# gk_midi_module.net
KiCad netlist of a schematic drawn in EAGLE
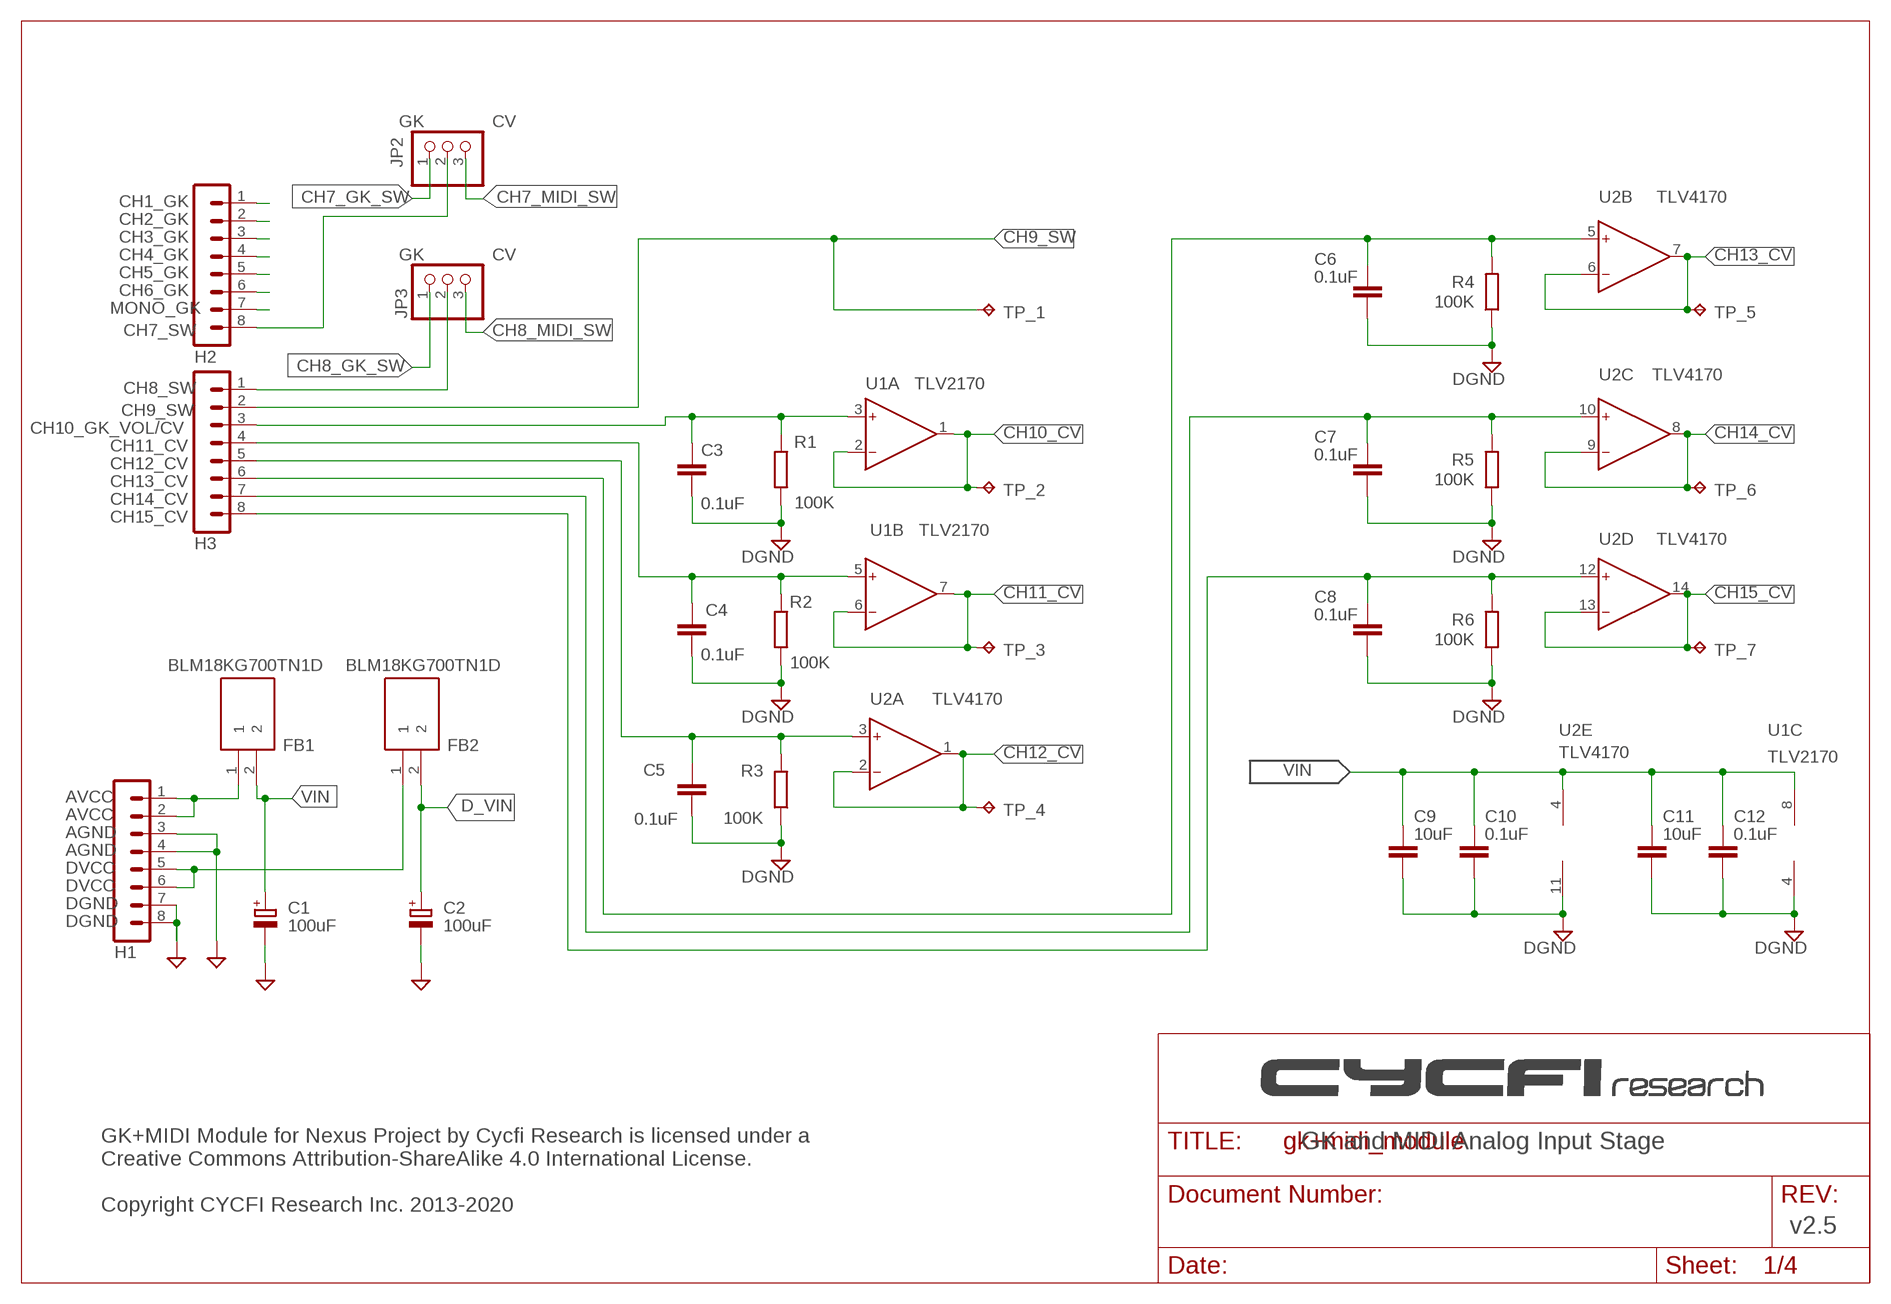
[diagram p0: schematic, sheet 1]
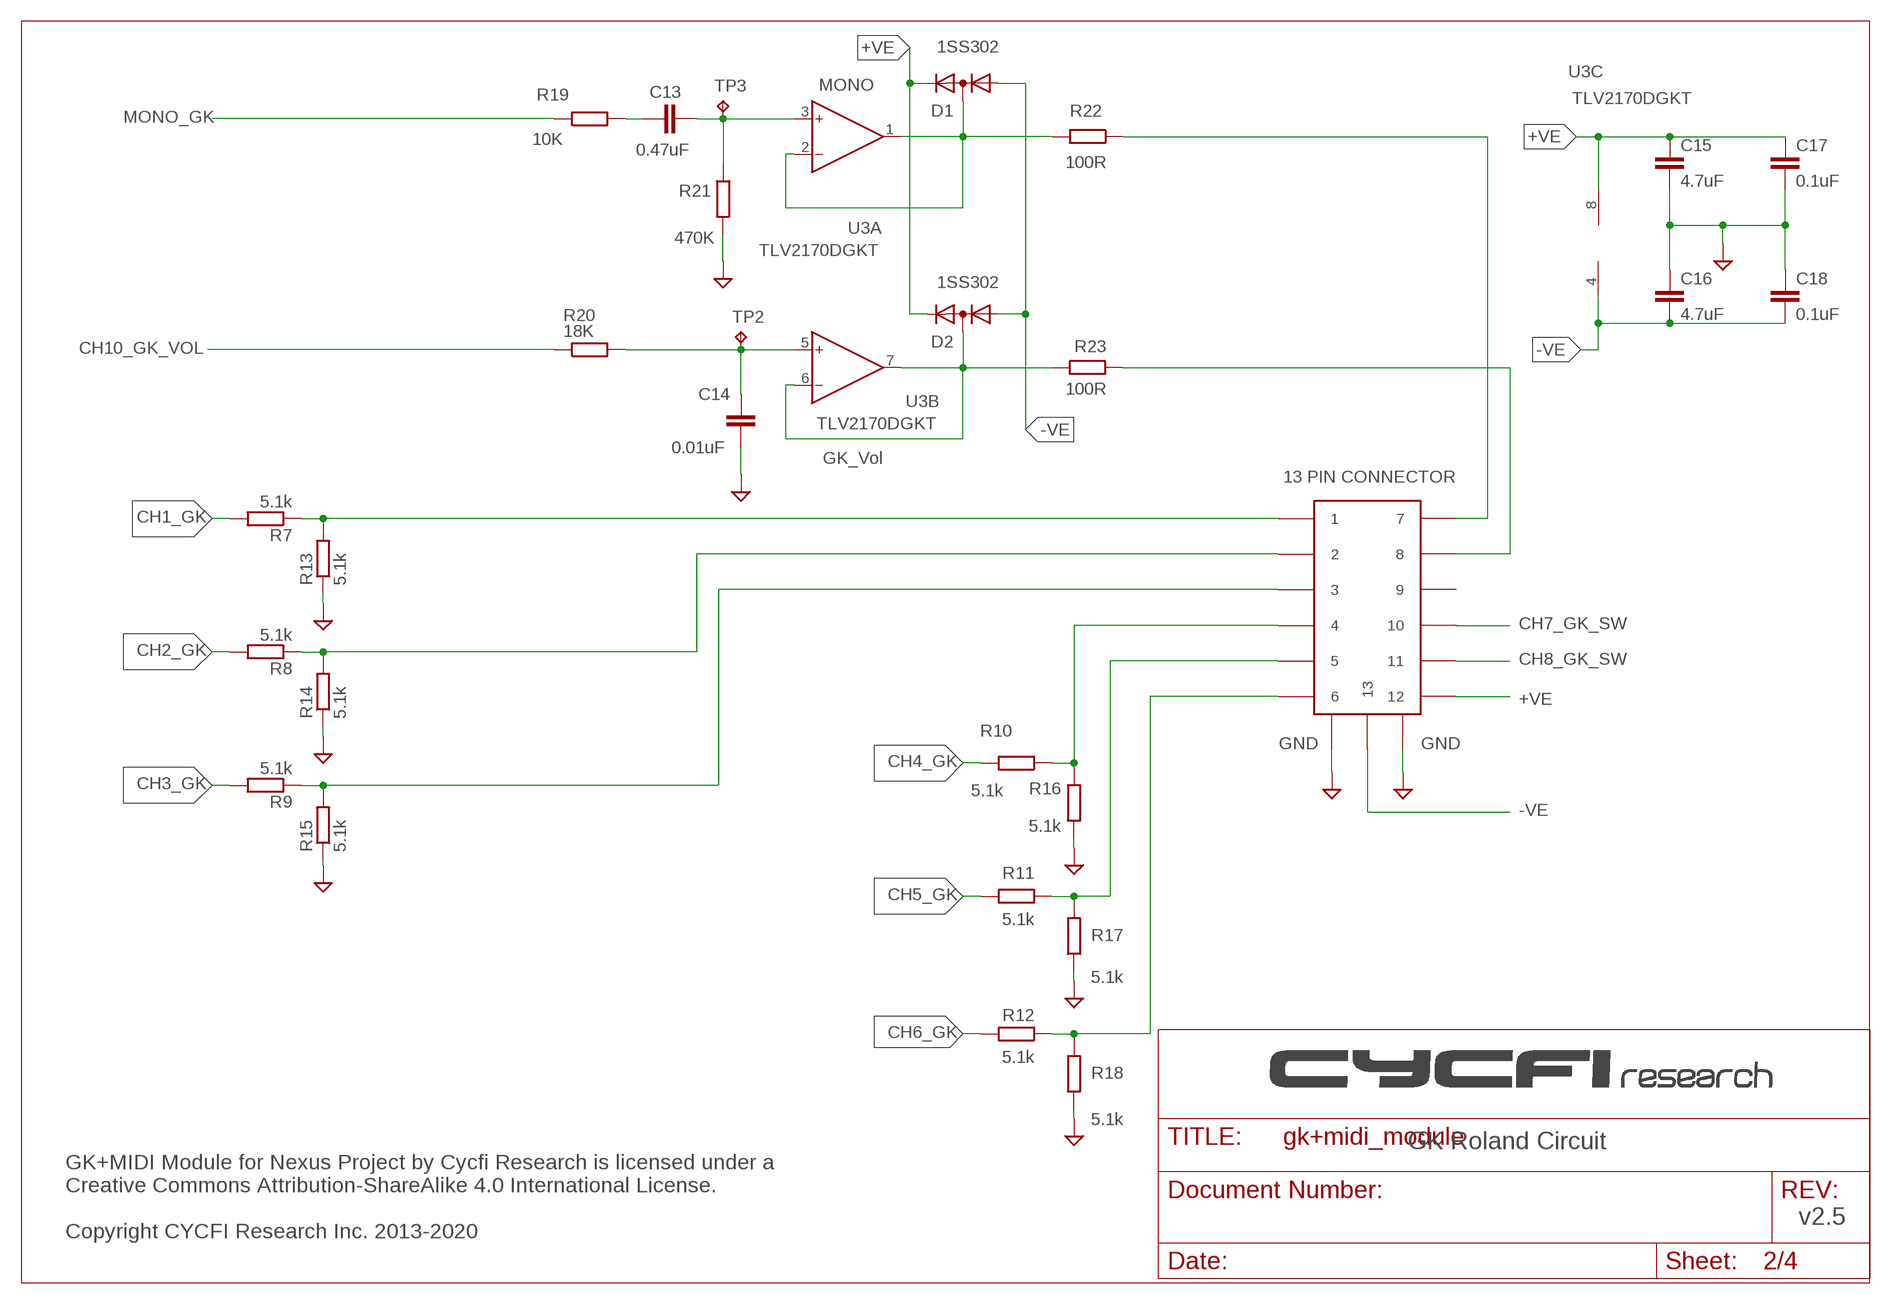
[diagram p1: schematic, sheet 2]
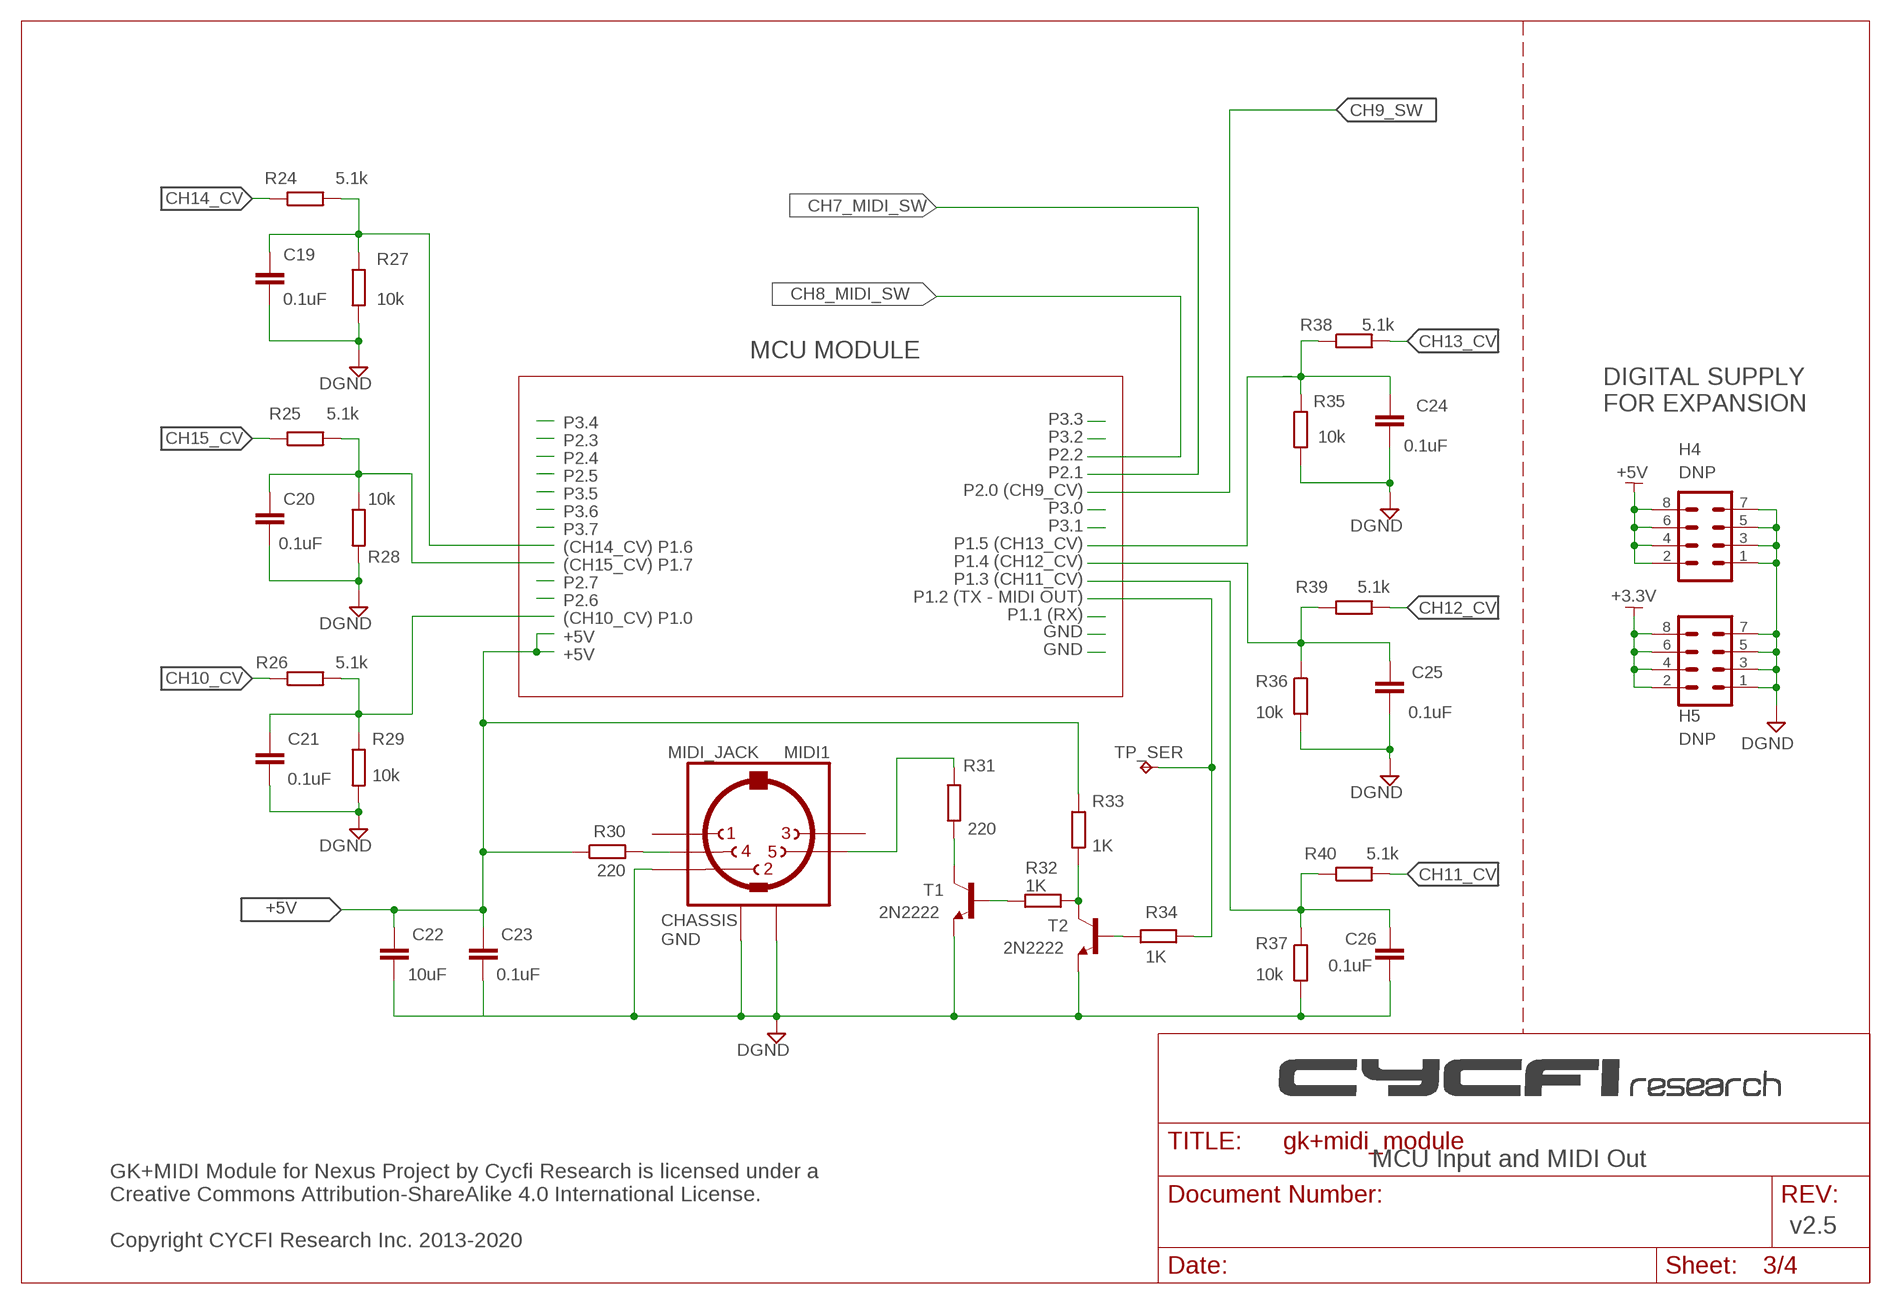
[diagram p2: schematic, sheet 3]
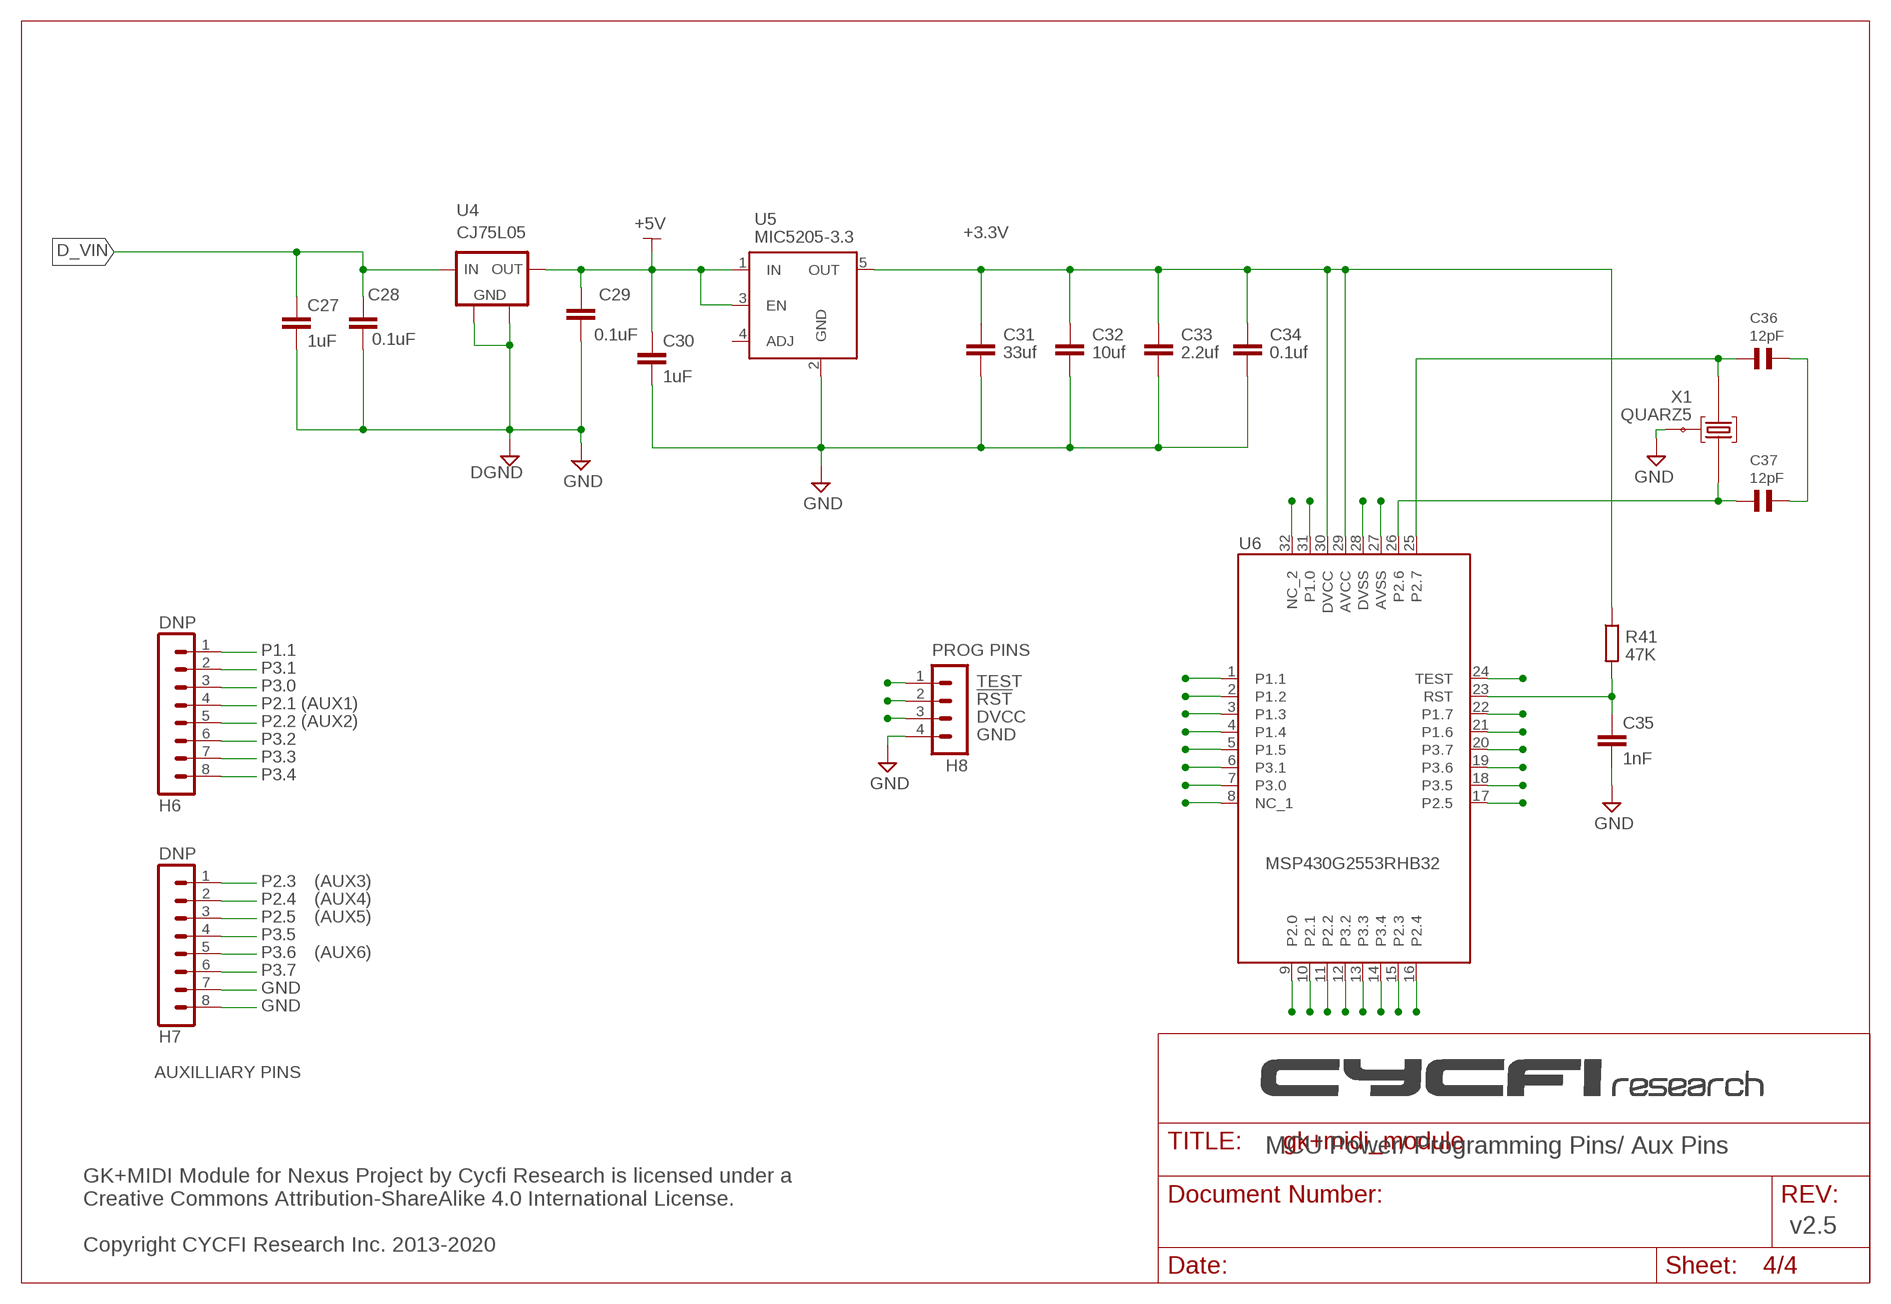
[diagram p3: schematic, sheet 4]

(export (version "E")
  (design (tool "Eeschema 10.0.6"))
  (components
    (comp (ref "C27")
      (value "1uF")
      (footprint "eagle-import:C0402")
      (libsource (lib "eagle-import") (part "C-EUC0402"))
    )
    (comp (ref "C28")
      (value "0.1uF")
      (footprint "eagle-import:C0603")
      (libsource (lib "eagle-import") (part "C-EUC0603"))
    )
    (comp (ref "C29")
      (value "0.1uF")
      (footprint "eagle-import:C0603")
      (libsource (lib "eagle-import") (part "C-EUC0603"))
    )
    (comp (ref "C30")
      (value "1uF")
      (footprint "eagle-import:C0402")
      (libsource (lib "eagle-import") (part "C-EUC0402"))
    )
    (comp (ref "C31")
      (value "33uf")
      (footprint "eagle-import:C0805")
      (libsource (lib "eagle-import") (part "C-EUC0805"))
    )
    (comp (ref "C32")
      (value "10uf")
      (footprint "eagle-import:C0805")
      (libsource (lib "eagle-import") (part "C-EUC0805"))
    )
    (comp (ref "C33")
      (value "2.2uf")
      (footprint "eagle-import:C0805")
      (libsource (lib "eagle-import") (part "C-EUC0805"))
    )
    (comp (ref "C34")
      (value "0.1uf")
      (footprint "eagle-import:C0603")
      (libsource (lib "eagle-import") (part "C-EUC0603"))
    )
    (comp (ref "C35")
      (value "1nF")
      (footprint "eagle-import:C0402")
      (libsource (lib "eagle-import") (part "C-EUC0402"))
    )
    (comp (ref "C36")
      (value "12pF")
      (footprint "eagle-import:0603")
      (libsource (lib "eagle-import") (part "C_SMD0603"))
    )
    (comp (ref "C37")
      (value "12pF")
      (footprint "eagle-import:0603")
      (libsource (lib "eagle-import") (part "C_SMD0603"))
    )
    (comp (ref "H6")
      (value "DNP")
      (footprint "eagle-import:MA08-1")
      (libsource (lib "eagle-import") (part "MA08-1"))
    )
    (comp (ref "H7")
      (value "DNP")
      (footprint "eagle-import:MA08-1")
      (libsource (lib "eagle-import") (part "MA08-1"))
    )
    (comp (ref "H8")
      (value "MA04-1")
      (footprint "eagle-import:MA04-1")
      (libsource (lib "eagle-import") (part "MA04-1"))
    )
    (comp (ref "R41")
      (value "47K")
      (footprint "eagle-import:R0402")
      (libsource (lib "eagle-import") (part "R-EU_R0402"))
    )
    (comp (ref "U4")
      (value "L78LXX")
      (footprint "eagle-import:SOT89")
      (libsource (lib "eagle-import") (part "L78LXX"))
    )
    (comp (ref "U5")
      (value "MIC5205-3.3")
      (footprint "eagle-import:SOT23-5")
      (fields (field (name "MF") "ALTERA CORPORATION") (field (name "MPN") "MIC5219BM5 TR"))
      (libsource (lib "eagle-import") (part "MIC5219BM5"))
    )
    (comp (ref "U6")
      (value "MSP430G2553RHB32")
      (footprint "eagle-import:QFN32")
      (libsource (lib "eagle-import") (part "MSP430G2553RHB32"))
    )
    (comp (ref "X1")
      (value "QUARZ5")
      (footprint "eagle-import:QUARZ5")
      (libsource (lib "eagle-import") (part "QUARZ5"))
    )
    (comp (ref "C1")
      (value "100uF")
      (footprint "eagle-import:153CLV-0505")
      (libsource (lib "eagle-import") (part "CPOL-EU153CLV-0505"))
    )
    (comp (ref "C2")
      (value "100uF")
      (footprint "eagle-import:153CLV-0505")
      (libsource (lib "eagle-import") (part "CPOL-EU153CLV-0505"))
    )
    (comp (ref "C3")
      (value "0.1uF")
      (footprint "eagle-import:C0603")
      (libsource (lib "eagle-import") (part "C-EUC0603"))
    )
    (comp (ref "C4")
      (value "0.1uF")
      (footprint "eagle-import:C0603")
      (libsource (lib "eagle-import") (part "C-EUC0603"))
    )
    (comp (ref "C5")
      (value "0.1uF")
      (footprint "eagle-import:C0603")
      (libsource (lib "eagle-import") (part "C-EUC0603"))
    )
    (comp (ref "C6")
      (value "0.1uF")
      (footprint "eagle-import:C0603")
      (libsource (lib "eagle-import") (part "C-EUC0603"))
    )
    (comp (ref "C7")
      (value "0.1uF")
      (footprint "eagle-import:C0603")
      (libsource (lib "eagle-import") (part "C-EUC0603"))
    )
    (comp (ref "C8")
      (value "0.1uF")
      (footprint "eagle-import:C0603")
      (libsource (lib "eagle-import") (part "C-EUC0603"))
    )
    (comp (ref "C9")
      (value "10uF")
      (footprint "eagle-import:C0805")
      (libsource (lib "eagle-import") (part "C-EUC0805"))
    )
    (comp (ref "C10")
      (value "0.1uF")
      (footprint "eagle-import:C0603")
      (libsource (lib "eagle-import") (part "C-EUC0603"))
    )
    (comp (ref "C11")
      (value "10uF")
      (footprint "eagle-import:C0805")
      (libsource (lib "eagle-import") (part "C-EUC0805"))
    )
    (comp (ref "C12")
      (value "0.1uF")
      (footprint "eagle-import:C0603")
      (libsource (lib "eagle-import") (part "C-EUC0603"))
    )
    (comp (ref "FB1")
      (value "BLM18KG700TN1D")
      (footprint "eagle-import:BEADC1608X75N")
      (fields (field (name "MOUSER_PART_NUMBER") "81-BLM18KG700TN1D"))
      (libsource (lib "eagle-import") (part "BLM18KG700TN1D"))
    )
    (comp (ref "FB2")
      (value "BLM18KG700TN1D")
      (footprint "eagle-import:BEADC1608X75N")
      (description "BLM18_N1D Series EMI Suppression Filter 70+/-25% at 100MHz 3.5A @85")
      (fields
        (field (name "MOUSER_PART_NUMBER") "81-BLM18KG700TN1D")
        (field (name "HEIGHT") "0.75mm")
        (field (name "MANUFACTURER_NAME") "Murata Electronics")
        (field (name "MANUFACTURER_PART_NUMBER") "BLM18KG700TN1D")
        (field (name "MOUSER_PART_NUMBER_1") "81-BLM18KG700TN1D")
        (field (name "MOUSER_PRICE-STOCK") "https://www.mouser.com/Search/Refine.aspx?Keyword=81-BLM18KG700TN1D")
      )
      (libsource (lib "eagle-import") (part "BLM18KG700TN1D"))
    )
    (comp (ref "H1")
      (value "MA08-1")
      (footprint "eagle-import:MA08-1")
      (libsource (lib "eagle-import") (part "MA08-1"))
    )
    (comp (ref "H2")
      (value "MA08-1")
      (footprint "eagle-import:MA08-1")
      (libsource (lib "eagle-import") (part "MA08-1"))
    )
    (comp (ref "H3")
      (value "MA08-1")
      (footprint "eagle-import:MA08-1")
      (libsource (lib "eagle-import") (part "MA08-1"))
    )
    (comp (ref "JP2")
      (value "PINHD-1X03_2.00")
      (footprint "eagle-import:1X03M")
      (libsource (lib "eagle-import") (part "PINHD-1X03_2.00"))
    )
    (comp (ref "JP3")
      (value "PINHD-1X03_2.00")
      (footprint "eagle-import:1X03M")
      (libsource (lib "eagle-import") (part "PINHD-1X03_2.00"))
    )
    (comp (ref "R1")
      (value "100K")
      (footprint "eagle-import:R0402")
      (libsource (lib "eagle-import") (part "R-EU_R0402"))
    )
    (comp (ref "R2")
      (value "100K")
      (footprint "eagle-import:R0402")
      (libsource (lib "eagle-import") (part "R-EU_R0402"))
    )
    (comp (ref "R3")
      (value "100K")
      (footprint "eagle-import:R0402")
      (libsource (lib "eagle-import") (part "R-EU_R0402"))
    )
    (comp (ref "R4")
      (value "100K")
      (footprint "eagle-import:R0402")
      (libsource (lib "eagle-import") (part "R-EU_R0402"))
    )
    (comp (ref "R5")
      (value "100K")
      (footprint "eagle-import:R0402")
      (libsource (lib "eagle-import") (part "R-EU_R0402"))
    )
    (comp (ref "R6")
      (value "100K")
      (footprint "eagle-import:R0402")
      (libsource (lib "eagle-import") (part "R-EU_R0402"))
    )
    (comp (ref "TP_1")
      (value "TPB1,27")
      (footprint "eagle-import:B1,27")
      (libsource (lib "eagle-import") (part "TPB1,27"))
    )
    (comp (ref "TP_2")
      (value "TPB1,27")
      (footprint "eagle-import:B1,27")
      (libsource (lib "eagle-import") (part "TPB1,27"))
    )
    (comp (ref "TP_3")
      (value "TPB1,27")
      (footprint "eagle-import:B1,27")
      (libsource (lib "eagle-import") (part "TPB1,27"))
    )
    (comp (ref "TP_4")
      (value "TPB1,27")
      (footprint "eagle-import:B1,27")
      (libsource (lib "eagle-import") (part "TPB1,27"))
    )
    (comp (ref "TP_5")
      (value "TPB1,27")
      (footprint "eagle-import:B1,27")
      (libsource (lib "eagle-import") (part "TPB1,27"))
    )
    (comp (ref "TP_6")
      (value "TPB1,27")
      (footprint "eagle-import:B1,27")
      (libsource (lib "eagle-import") (part "TPB1,27"))
    )
    (comp (ref "TP_7")
      (value "TPB1,27")
      (footprint "eagle-import:B1,27")
      (libsource (lib "eagle-import") (part "TPB1,27"))
    )
    (comp (ref "U1")
      (value "TLV2170DGKT")
      (footprint "eagle-import:MSOP8")
      (libsource (lib "eagle-import") (part "TLV2170DGKT"))
    )
    (comp (ref "U2")
      (value "LMV324")
      (footprint "eagle-import:SSOP-14")
      (libsource (lib "eagle-import") (part "LMV324"))
    )
    (comp (ref "C19")
      (value "0.1uF")
      (footprint "eagle-import:C0603")
      (libsource (lib "eagle-import") (part "C-EUC0603"))
    )
    (comp (ref "C20")
      (value "0.1uF")
      (footprint "eagle-import:C0603")
      (libsource (lib "eagle-import") (part "C-EUC0603"))
    )
    (comp (ref "C21")
      (value "0.1uF")
      (footprint "eagle-import:C0603")
      (libsource (lib "eagle-import") (part "C-EUC0603"))
    )
    (comp (ref "C22")
      (value "10uF")
      (footprint "eagle-import:C0805")
      (libsource (lib "eagle-import") (part "C-EUC0805"))
    )
    (comp (ref "C23")
      (value "0.1uF")
      (footprint "eagle-import:C0603")
      (libsource (lib "eagle-import") (part "C-EUC0603"))
    )
    (comp (ref "C24")
      (value "0.1uF")
      (footprint "eagle-import:C0603")
      (libsource (lib "eagle-import") (part "C-EUC0603"))
    )
    (comp (ref "C25")
      (value "0.1uF")
      (footprint "eagle-import:C0603")
      (libsource (lib "eagle-import") (part "C-EUC0603"))
    )
    (comp (ref "C26")
      (value "0.1uF")
      (footprint "eagle-import:C0603")
      (libsource (lib "eagle-import") (part "C-EUC0603"))
    )
    (comp (ref "H4")
      (value "DNP")
      (footprint "eagle-import:MA04-2")
      (libsource (lib "eagle-import") (part "MA04-2"))
    )
    (comp (ref "H5")
      (value "DNP")
      (footprint "eagle-import:MA04-2")
      (libsource (lib "eagle-import") (part "MA04-2"))
    )
    (comp (ref "MIDI1")
      (value "MIDI_JACK")
      (footprint "eagle-import:MIDI_JACK")
      (libsource (lib "eagle-import") (part "MIDI_JACK"))
    )
    (comp (ref "R24")
      (value "5.1k")
      (footprint "eagle-import:R0402")
      (libsource (lib "eagle-import") (part "R-EU_R0402"))
    )
    (comp (ref "R25")
      (value "5.1k")
      (footprint "eagle-import:R0402")
      (libsource (lib "eagle-import") (part "R-EU_R0402"))
    )
    (comp (ref "R26")
      (value "5.1k")
      (footprint "eagle-import:R0402")
      (libsource (lib "eagle-import") (part "R-EU_R0402"))
    )
    (comp (ref "R27")
      (value "10k")
      (footprint "eagle-import:R0402")
      (libsource (lib "eagle-import") (part "R-EU_R0402"))
    )
    (comp (ref "R28")
      (value "10k")
      (footprint "eagle-import:R0402")
      (libsource (lib "eagle-import") (part "R-EU_R0402"))
    )
    (comp (ref "R29")
      (value "10k")
      (footprint "eagle-import:R0402")
      (libsource (lib "eagle-import") (part "R-EU_R0402"))
    )
    (comp (ref "R30")
      (value "220")
      (footprint "eagle-import:R0402")
      (libsource (lib "eagle-import") (part "R-EU_R0402"))
    )
    (comp (ref "R31")
      (value "220")
      (footprint "eagle-import:R0402")
      (libsource (lib "eagle-import") (part "R-EU_R0402"))
    )
    (comp (ref "R32")
      (value "1K")
      (footprint "eagle-import:R0402")
      (libsource (lib "eagle-import") (part "R-EU_R0402"))
    )
    (comp (ref "R33")
      (value "1K")
      (footprint "eagle-import:R0402")
      (libsource (lib "eagle-import") (part "R-EU_R0402"))
    )
    (comp (ref "R34")
      (value "1K")
      (footprint "eagle-import:R0402")
      (libsource (lib "eagle-import") (part "R-EU_R0402"))
    )
    (comp (ref "R35")
      (value "10k")
      (footprint "eagle-import:R0402")
      (libsource (lib "eagle-import") (part "R-EU_R0402"))
    )
    (comp (ref "R36")
      (value "10k")
      (footprint "eagle-import:R0402")
      (libsource (lib "eagle-import") (part "R-EU_R0402"))
    )
    (comp (ref "R37")
      (value "10k")
      (footprint "eagle-import:R0402")
      (libsource (lib "eagle-import") (part "R-EU_R0402"))
    )
    (comp (ref "R38")
      (value "5.1k")
      (footprint "eagle-import:R0402")
      (libsource (lib "eagle-import") (part "R-EU_R0402"))
    )
    (comp (ref "R39")
      (value "5.1k")
      (footprint "eagle-import:R0402")
      (libsource (lib "eagle-import") (part "R-EU_R0402"))
    )
    (comp (ref "R40")
      (value "5.1k")
      (footprint "eagle-import:R0402")
      (libsource (lib "eagle-import") (part "R-EU_R0402"))
    )
    (comp (ref "T1")
      (value "2N2222")
      (footprint "eagle-import:SOT23-3")
      (libsource (lib "eagle-import") (part "TRAN-MMBT2222A"))
    )
    (comp (ref "T2")
      (value "2N2222")
      (footprint "eagle-import:SOT23-3")
      (libsource (lib "eagle-import") (part "TRAN-MMBT2222A"))
    )
    (comp (ref "TP_SER")
      (value "TPB1,27")
      (footprint "eagle-import:B1,27")
      (libsource (lib "eagle-import") (part "TPB1,27"))
    )
    (comp (ref "C13")
      (value "0.47uF")
      (footprint "eagle-import:C0603")
      (libsource (lib "eagle-import") (part "C-EUC0603"))
    )
    (comp (ref "C14")
      (value "0.01uF")
      (footprint "eagle-import:C0402")
      (libsource (lib "eagle-import") (part "C-EUC0402"))
    )
    (comp (ref "C15")
      (value "4.7uF")
      (footprint "eagle-import:C0603")
      (libsource (lib "eagle-import") (part "C-EUC0603"))
    )
    (comp (ref "C16")
      (value "4.7uF")
      (footprint "eagle-import:C0603")
      (libsource (lib "eagle-import") (part "C-EUC0603"))
    )
    (comp (ref "C17")
      (value "0.1uF")
      (footprint "eagle-import:C0603")
      (libsource (lib "eagle-import") (part "C-EUC0603"))
    )
    (comp (ref "C18")
      (value "0.1uF")
      (footprint "eagle-import:C0603")
      (libsource (lib "eagle-import") (part "C-EUC0603"))
    )
    (comp (ref "D1")
      (value "1SS302")
      (footprint "eagle-import:SC70-3")
      (libsource (lib "eagle-import") (part "1SS302"))
    )
    (comp (ref "D2")
      (value "1SS302")
      (footprint "eagle-import:SC70-3")
      (libsource (lib "eagle-import") (part "1SS302"))
    )
    (comp (ref "R7")
      (value "5.1k")
      (footprint "eagle-import:R0402")
      (libsource (lib "eagle-import") (part "R-EU_R0402"))
    )
    (comp (ref "R8")
      (value "5.1k")
      (footprint "eagle-import:R0402")
      (libsource (lib "eagle-import") (part "R-EU_R0402"))
    )
    (comp (ref "R9")
      (value "5.1k")
      (footprint "eagle-import:R0402")
      (libsource (lib "eagle-import") (part "R-EU_R0402"))
    )
    (comp (ref "R10")
      (value "5.1k")
      (footprint "eagle-import:R0402")
      (libsource (lib "eagle-import") (part "R-EU_R0402"))
    )
    (comp (ref "R11")
      (value "5.1k")
      (footprint "eagle-import:R0402")
      (libsource (lib "eagle-import") (part "R-EU_R0402"))
    )
    (comp (ref "R12")
      (value "5.1k")
      (footprint "eagle-import:R0402")
      (libsource (lib "eagle-import") (part "R-EU_R0402"))
    )
    (comp (ref "R13")
      (value "5.1k")
      (footprint "eagle-import:R0402")
      (libsource (lib "eagle-import") (part "R-EU_R0402"))
    )
    (comp (ref "R14")
      (value "5.1k")
      (footprint "eagle-import:R0402")
      (libsource (lib "eagle-import") (part "R-EU_R0402"))
    )
    (comp (ref "R15")
      (value "5.1k")
      (footprint "eagle-import:R0402")
      (libsource (lib "eagle-import") (part "R-EU_R0402"))
    )
    (comp (ref "R16")
      (value "5.1k")
      (footprint "eagle-import:R0402")
      (libsource (lib "eagle-import") (part "R-EU_R0402"))
    )
    (comp (ref "R17")
      (value "5.1k")
      (footprint "eagle-import:R0402")
      (libsource (lib "eagle-import") (part "R-EU_R0402"))
    )
    (comp (ref "R18")
      (value "5.1k")
      (footprint "eagle-import:R0402")
      (libsource (lib "eagle-import") (part "R-EU_R0402"))
    )
    (comp (ref "R19")
      (value "10K")
      (footprint "eagle-import:R0402")
      (libsource (lib "eagle-import") (part "R-EU_R0402"))
    )
    (comp (ref "R20")
      (value "18K")
      (footprint "eagle-import:R0402")
      (libsource (lib "eagle-import") (part "R-EU_R0402"))
    )
    (comp (ref "R21")
      (value "470K")
      (footprint "eagle-import:R0402")
      (libsource (lib "eagle-import") (part "R-EU_R0402"))
    )
    (comp (ref "R22")
      (value "100R")
      (footprint "eagle-import:R0402")
      (libsource (lib "eagle-import") (part "R-EU_R0402"))
    )
    (comp (ref "R23")
      (value "100R")
      (footprint "eagle-import:R0402")
      (libsource (lib "eagle-import") (part "R-EU_R0402"))
    )
    (comp (ref "TP2")
      (value "TPB1,27")
      (footprint "eagle-import:B1,27")
      (libsource (lib "eagle-import") (part "TPB1,27"))
    )
    (comp (ref "TP3")
      (value "TPB1,27")
      (footprint "eagle-import:B1,27")
      (libsource (lib "eagle-import") (part "TPB1,27"))
    )
    (comp (ref "U$1")
      (value "13P_MIDI_2")
      (footprint "eagle-import:13P-MIDI-2")
      (libsource (lib "eagle-import") (part "13P_MIDI_2"))
    )
    (comp (ref "U3")
      (value "TLV2170DGKT")
      (footprint "eagle-import:MSOP8")
      (libsource (lib "eagle-import") (part "TLV2170DGKT"))
    )
  )
  (nets
    (net (code "1") (name "+3.3V") (class "Default")
      (node (ref "C31") (pin "1") (pinfunction "1_1") (pintype "passive"))
      (node (ref "C32") (pin "1") (pinfunction "1_1") (pintype "passive"))
      (node (ref "C33") (pin "1") (pinfunction "1_1") (pintype "passive"))
      (node (ref "C34") (pin "1") (pinfunction "1_1") (pintype "passive"))
      (node (ref "H5") (pin "2") (pinfunction "2_2") (pintype "passive"))
      (node (ref "H5") (pin "4") (pinfunction "4_4") (pintype "passive"))
      (node (ref "H5") (pin "6") (pinfunction "6_6") (pintype "passive"))
      (node (ref "H5") (pin "8") (pinfunction "8_8") (pintype "passive"))
      (node (ref "H8") (pin "3") (pinfunction "3_3") (pintype "passive"))
      (node (ref "R41") (pin "1") (pinfunction "1_1") (pintype "passive"))
      (node (ref "U5") (pin "5") (pinfunction "OUT_5") (pintype "output"))
      (node (ref "U6") (pin "29") (pinfunction "AVCC_29") (pintype "bidirectional"))
      (node (ref "U6") (pin "30") (pinfunction "DVCC_30") (pintype "bidirectional"))
    )
    (net (code "2") (name "+5V") (class "Default")
      (node (ref "C22") (pin "1") (pinfunction "1_1") (pintype "passive"))
      (node (ref "C23") (pin "1") (pinfunction "1_1") (pintype "passive"))
      (node (ref "C29") (pin "1") (pinfunction "1_1") (pintype "passive"))
      (node (ref "C30") (pin "1") (pinfunction "1_1") (pintype "passive"))
      (node (ref "H4") (pin "2") (pinfunction "2_2") (pintype "passive"))
      (node (ref "H4") (pin "4") (pinfunction "4_4") (pintype "passive"))
      (node (ref "H4") (pin "6") (pinfunction "6_6") (pintype "passive"))
      (node (ref "H4") (pin "8") (pinfunction "8_8") (pintype "passive"))
      (node (ref "R30") (pin "1") (pinfunction "1_1") (pintype "passive"))
      (node (ref "R33") (pin "2") (pinfunction "2_2") (pintype "passive"))
      (node (ref "U4") (pin "1") (pinfunction "IN_1") (pintype "input"))
      (node (ref "U5") (pin "1") (pinfunction "IN_1") (pintype "input"))
      (node (ref "U5") (pin "3") (pinfunction "EN_3") (pintype "input"))
    )
    (net (code "3") (name "+VE") (class "Default")
      (node (ref "C15") (pin "1") (pinfunction "1_1") (pintype "passive"))
      (node (ref "C17") (pin "1") (pinfunction "1_1") (pintype "passive"))
      (node (ref "D1") (pin "2") (pinfunction "K_2") (pintype "passive"))
      (node (ref "D2") (pin "2") (pinfunction "K_2") (pintype "passive"))
      (node (ref "U$1") (pin "12") (pinfunction "12_12") (pintype "bidirectional"))
      (node (ref "U3") (pin "8") (pinfunction "V+_8") (pintype "power_in"))
    )
    (net (code "4") (name "-VE") (class "Default")
      (node (ref "C16") (pin "2") (pinfunction "2_2") (pintype "passive"))
      (node (ref "C18") (pin "2") (pinfunction "2_2") (pintype "passive"))
      (node (ref "D1") (pin "1") (pinfunction "A_1") (pintype "passive"))
      (node (ref "D2") (pin "1") (pinfunction "A_1") (pintype "passive"))
      (node (ref "U$1") (pin "13") (pinfunction "13_13") (pintype "bidirectional"))
      (node (ref "U3") (pin "4") (pinfunction "V-_4") (pintype "power_in"))
    )
    (net (code "5") (name "AVCC") (class "Default")
      (node (ref "FB1") (pin "1") (pinfunction "1_1") (pintype "bidirectional"))
      (node (ref "H1") (pin "1") (pinfunction "1_1") (pintype "passive"))
      (node (ref "H1") (pin "2") (pinfunction "2_2") (pintype "passive"))
    )
    (net (code "6") (name "CH1_GK") (class "Default")
      (node (ref "H2") (pin "1") (pinfunction "1_1") (pintype "passive"))
      (node (ref "R7") (pin "2") (pinfunction "2_2") (pintype "passive"))
    )
    (net (code "7") (name "CH2_GK") (class "Default")
      (node (ref "H2") (pin "2") (pinfunction "2_2") (pintype "passive"))
      (node (ref "R8") (pin "2") (pinfunction "2_2") (pintype "passive"))
    )
    (net (code "8") (name "CH3_GK") (class "Default")
      (node (ref "H2") (pin "3") (pinfunction "3_3") (pintype "passive"))
      (node (ref "R9") (pin "2") (pinfunction "2_2") (pintype "passive"))
    )
    (net (code "9") (name "CH4_GK") (class "Default")
      (node (ref "H2") (pin "4") (pinfunction "4_4") (pintype "passive"))
      (node (ref "R10") (pin "2") (pinfunction "2_2") (pintype "passive"))
    )
    (net (code "10") (name "CH5_GK") (class "Default")
      (node (ref "H2") (pin "5") (pinfunction "5_5") (pintype "passive"))
      (node (ref "R11") (pin "2") (pinfunction "2_2") (pintype "passive"))
    )
    (net (code "11") (name "CH6_GK") (class "Default")
      (node (ref "H2") (pin "6") (pinfunction "6_6") (pintype "passive"))
      (node (ref "R12") (pin "2") (pinfunction "2_2") (pintype "passive"))
    )
    (net (code "12") (name "CH7_GK_SW") (class "Default")
      (node (ref "JP2") (pin "1") (pinfunction "1_1") (pintype "passive"))
      (node (ref "U$1") (pin "10") (pinfunction "10_10") (pintype "bidirectional"))
    )
    (net (code "13") (name "CH7_MIDI_SW") (class "Default")
      (node (ref "H6") (pin "4") (pinfunction "4_4") (pintype "passive"))
      (node (ref "JP2") (pin "3") (pinfunction "3_3") (pintype "passive"))
      (node (ref "U6") (pin "10") (pinfunction "P2.1_10") (pintype "bidirectional"))
    )
    (net (code "14") (name "CH8_GK_SW") (class "Default")
      (node (ref "JP3") (pin "1") (pinfunction "1_1") (pintype "passive"))
      (node (ref "U$1") (pin "11") (pinfunction "11_11") (pintype "bidirectional"))
    )
    (net (code "15") (name "CH8_MIDI_SW") (class "Default")
      (node (ref "H6") (pin "5") (pinfunction "5_5") (pintype "passive"))
      (node (ref "JP3") (pin "3") (pinfunction "3_3") (pintype "passive"))
      (node (ref "U6") (pin "11") (pinfunction "P2.2_11") (pintype "bidirectional"))
    )
    (net (code "16") (name "CH9_SW") (class "Default")
      (node (ref "H3") (pin "2") (pinfunction "2_2") (pintype "passive"))
      (node (ref "TP_1") (pin "TP") (pinfunction "TP_TP") (pintype "input"))
      (node (ref "U6") (pin "9") (pinfunction "P2.0_9") (pintype "bidirectional"))
    )
    (net (code "17") (name "CH10_CV") (class "Default")
      (node (ref "R26") (pin "1") (pinfunction "1_1") (pintype "passive"))
      (node (ref "TP_2") (pin "TP") (pinfunction "TP_TP") (pintype "input"))
      (node (ref "U1") (pin "1") (pinfunction "OUT_1") (pintype "output"))
      (node (ref "U1") (pin "2") (pinfunction "IN-_2") (pintype "input"))
    )
    (net (code "18") (name "CH10_GK_VOL") (class "Default")
      (node (ref "C3") (pin "1") (pinfunction "1_1") (pintype "passive"))
      (node (ref "H3") (pin "3") (pinfunction "3_3") (pintype "passive"))
      (node (ref "R1") (pin "2") (pinfunction "2_2") (pintype "passive"))
      (node (ref "R20") (pin "1") (pinfunction "1_1") (pintype "passive"))
      (node (ref "U1") (pin "3") (pinfunction "IN+_3") (pintype "input"))
    )
    (net (code "19") (name "CH11_CV") (class "Default")
      (node (ref "R40") (pin "2") (pinfunction "2_2") (pintype "passive"))
      (node (ref "TP_3") (pin "TP") (pinfunction "TP_TP") (pintype "input"))
      (node (ref "U1") (pin "6") (pinfunction "IN-_6") (pintype "input"))
      (node (ref "U1") (pin "7") (pinfunction "OUT_7") (pintype "output"))
    )
    (net (code "20") (name "CH12_CV") (class "Default")
      (node (ref "R39") (pin "2") (pinfunction "2_2") (pintype "passive"))
      (node (ref "TP_4") (pin "TP") (pinfunction "TP_TP") (pintype "input"))
      (node (ref "U2") (pin "1") (pinfunction "OUT_1") (pintype "output"))
      (node (ref "U2") (pin "2") (pinfunction "IN-_2") (pintype "input"))
    )
    (net (code "21") (name "CH13_CV") (class "Default")
      (node (ref "R38") (pin "2") (pinfunction "2_2") (pintype "passive"))
      (node (ref "TP_5") (pin "TP") (pinfunction "TP_TP") (pintype "input"))
      (node (ref "U2") (pin "6") (pinfunction "IN-_6") (pintype "input"))
      (node (ref "U2") (pin "7") (pinfunction "OUT_7") (pintype "output"))
    )
    (net (code "22") (name "CH14_CV") (class "Default")
      (node (ref "R24") (pin "1") (pinfunction "1_1") (pintype "passive"))
      (node (ref "TP_6") (pin "TP") (pinfunction "TP_TP") (pintype "input"))
      (node (ref "U2") (pin "8") (pinfunction "OUT_8") (pintype "output"))
      (node (ref "U2") (pin "9") (pinfunction "IN-_9") (pintype "input"))
    )
    (net (code "23") (name "CH15_CV") (class "Default")
      (node (ref "R25") (pin "1") (pinfunction "1_1") (pintype "passive"))
      (node (ref "TP_7") (pin "TP") (pinfunction "TP_TP") (pintype "input"))
      (node (ref "U2") (pin "13") (pinfunction "IN-_13") (pintype "input"))
      (node (ref "U2") (pin "14") (pinfunction "OUT_14") (pintype "output"))
    )
    (net (code "24") (name "DVCC") (class "Default")
      (node (ref "FB2") (pin "1") (pinfunction "1_1") (pintype "bidirectional"))
      (node (ref "H1") (pin "5") (pinfunction "5_5") (pintype "passive"))
      (node (ref "H1") (pin "6") (pinfunction "6_6") (pintype "passive"))
    )
    (net (code "25") (name "D_VIN") (class "Default")
      (node (ref "C2") (pin "+") (pinfunction "+_+") (pintype "passive"))
      (node (ref "C27") (pin "1") (pinfunction "1_1") (pintype "passive"))
      (node (ref "C28") (pin "1") (pinfunction "1_1") (pintype "passive"))
      (node (ref "FB2") (pin "2") (pinfunction "2_2") (pintype "bidirectional"))
      (node (ref "U4") (pin "3") (pinfunction "OUT_3") (pintype "passive"))
    )
    (net (code "26") (name "GND") (class "Default")
      (node (ref "C1") (pin "-") (pinfunction "-_-") (pintype "passive"))
      (node (ref "C10") (pin "2") (pinfunction "2_2") (pintype "passive"))
      (node (ref "C11") (pin "2") (pinfunction "2_2") (pintype "passive"))
      (node (ref "C12") (pin "2") (pinfunction "2_2") (pintype "passive"))
      (node (ref "C14") (pin "2") (pinfunction "2_2") (pintype "passive"))
      (node (ref "C15") (pin "2") (pinfunction "2_2") (pintype "passive"))
      (node (ref "C16") (pin "1") (pinfunction "1_1") (pintype "passive"))
      (node (ref "C17") (pin "2") (pinfunction "2_2") (pintype "passive"))
      (node (ref "C18") (pin "1") (pinfunction "1_1") (pintype "passive"))
      (node (ref "C19") (pin "2") (pinfunction "2_2") (pintype "passive"))
      (node (ref "C2") (pin "-") (pinfunction "-_-") (pintype "passive"))
      (node (ref "C20") (pin "2") (pinfunction "2_2") (pintype "passive"))
      (node (ref "C21") (pin "2") (pinfunction "2_2") (pintype "passive"))
      (node (ref "C22") (pin "2") (pinfunction "2_2") (pintype "passive"))
      (node (ref "C23") (pin "2") (pinfunction "2_2") (pintype "passive"))
      (node (ref "C24") (pin "2") (pinfunction "2_2") (pintype "passive"))
      (node (ref "C25") (pin "2") (pinfunction "2_2") (pintype "passive"))
      (node (ref "C26") (pin "2") (pinfunction "2_2") (pintype "passive"))
      (node (ref "C27") (pin "2") (pinfunction "2_2") (pintype "passive"))
      (node (ref "C28") (pin "2") (pinfunction "2_2") (pintype "passive"))
      (node (ref "C29") (pin "2") (pinfunction "2_2") (pintype "passive"))
      (node (ref "C3") (pin "2") (pinfunction "2_2") (pintype "passive"))
      (node (ref "C30") (pin "2") (pinfunction "2_2") (pintype "passive"))
      (node (ref "C31") (pin "2") (pinfunction "2_2") (pintype "passive"))
      (node (ref "C32") (pin "2") (pinfunction "2_2") (pintype "passive"))
      (node (ref "C33") (pin "2") (pinfunction "2_2") (pintype "passive"))
      (node (ref "C34") (pin "2") (pinfunction "2_2") (pintype "passive"))
      (node (ref "C35") (pin "2") (pinfunction "2_2") (pintype "passive"))
      (node (ref "C36") (pin "1") (pinfunction "1_1") (pintype "passive"))
      (node (ref "C37") (pin "1") (pinfunction "1_1") (pintype "passive"))
      (node (ref "C4") (pin "2") (pinfunction "2_2") (pintype "passive"))
      (node (ref "C5") (pin "2") (pinfunction "2_2") (pintype "passive"))
      (node (ref "C6") (pin "2") (pinfunction "2_2") (pintype "passive"))
      (node (ref "C7") (pin "2") (pinfunction "2_2") (pintype "passive"))
      (node (ref "C8") (pin "2") (pinfunction "2_2") (pintype "passive"))
      (node (ref "C9") (pin "2") (pinfunction "2_2") (pintype "passive"))
      (node (ref "H1") (pin "3") (pinfunction "3_3") (pintype "passive"))
      (node (ref "H1") (pin "4") (pinfunction "4_4") (pintype "passive"))
      (node (ref "H1") (pin "7") (pinfunction "7_7") (pintype "passive"))
      (node (ref "H1") (pin "8") (pinfunction "8_8") (pintype "passive"))
      (node (ref "H4") (pin "1") (pinfunction "1_1") (pintype "passive"))
      (node (ref "H4") (pin "3") (pinfunction "3_3") (pintype "passive"))
      (node (ref "H4") (pin "5") (pinfunction "5_5") (pintype "passive"))
      (node (ref "H4") (pin "7") (pinfunction "7_7") (pintype "passive"))
      (node (ref "H5") (pin "1") (pinfunction "1_1") (pintype "passive"))
      (node (ref "H5") (pin "3") (pinfunction "3_3") (pintype "passive"))
      (node (ref "H5") (pin "5") (pinfunction "5_5") (pintype "passive"))
      (node (ref "H5") (pin "7") (pinfunction "7_7") (pintype "passive"))
      (node (ref "H7") (pin "7") (pinfunction "7_7") (pintype "passive"))
      (node (ref "H7") (pin "8") (pinfunction "8_8") (pintype "passive"))
      (node (ref "H8") (pin "4") (pinfunction "4_4") (pintype "passive"))
      (node (ref "MIDI1") (pin "2") (pinfunction "2_2") (pintype "passive"))
      (node (ref "MIDI1") (pin "G1") (pinfunction "G1_G1") (pintype "bidirectional"))
      (node (ref "MIDI1") (pin "G2") (pinfunction "G2_G2") (pintype "bidirectional"))
      (node (ref "R1") (pin "1") (pinfunction "1_1") (pintype "passive"))
      (node (ref "R13") (pin "1") (pinfunction "1_1") (pintype "passive"))
      (node (ref "R14") (pin "1") (pinfunction "1_1") (pintype "passive"))
      (node (ref "R15") (pin "1") (pinfunction "1_1") (pintype "passive"))
      (node (ref "R16") (pin "1") (pinfunction "1_1") (pintype "passive"))
      (node (ref "R17") (pin "1") (pinfunction "1_1") (pintype "passive"))
      (node (ref "R18") (pin "1") (pinfunction "1_1") (pintype "passive"))
      (node (ref "R2") (pin "1") (pinfunction "1_1") (pintype "passive"))
      (node (ref "R21") (pin "2") (pinfunction "2_2") (pintype "passive"))
      (node (ref "R27") (pin "2") (pinfunction "2_2") (pintype "passive"))
      (node (ref "R28") (pin "2") (pinfunction "2_2") (pintype "passive"))
      (node (ref "R29") (pin "2") (pinfunction "2_2") (pintype "passive"))
      (node (ref "R3") (pin "1") (pinfunction "1_1") (pintype "passive"))
      (node (ref "R35") (pin "2") (pinfunction "2_2") (pintype "passive"))
      (node (ref "R36") (pin "2") (pinfunction "2_2") (pintype "passive"))
      (node (ref "R37") (pin "2") (pinfunction "2_2") (pintype "passive"))
      (node (ref "R4") (pin "1") (pinfunction "1_1") (pintype "passive"))
      (node (ref "R5") (pin "1") (pinfunction "1_1") (pintype "passive"))
      (node (ref "R6") (pin "1") (pinfunction "1_1") (pintype "passive"))
      (node (ref "T1") (pin "2") (pinfunction "E_2") (pintype "passive"))
      (node (ref "T2") (pin "2") (pinfunction "E_2") (pintype "passive"))
      (node (ref "U$1") (pin "P$1") (pinfunction "14_P$1") (pintype "bidirectional"))
      (node (ref "U$1") (pin "P$2") (pinfunction "15_P$2") (pintype "bidirectional"))
      (node (ref "U1") (pin "4") (pinfunction "V-_4") (pintype "power_in"))
      (node (ref "U2") (pin "11") (pinfunction "V-_11") (pintype "power_in"))
      (node (ref "U4") (pin "2") (pinfunction "GND_2") (pintype "input"))
      (node (ref "U4") (pin "2@1") (pinfunction "GND1_2@1") (pintype "input"))
      (node (ref "U5") (pin "2") (pinfunction "GND_2") (pintype "power_in"))
      (node (ref "U6") (pin "27") (pinfunction "AVSS_27") (pintype "bidirectional"))
      (node (ref "U6") (pin "28") (pinfunction "DVSS_28") (pintype "power_in"))
      (node (ref "X1") (pin "GND@0") (pinfunction "0_GND@0") (pintype "passive"))
    )
    (net (code "27") (name "MONO_GK") (class "Default")
      (node (ref "H2") (pin "7") (pinfunction "7_7") (pintype "passive"))
      (node (ref "R19") (pin "1") (pinfunction "1_1") (pintype "passive"))
    )
    (net (code "28") (name "Net-(C13-Pad2)") (class "Default")
      (node (ref "C13") (pin "2") (pinfunction "2_2") (pintype "passive"))
      (node (ref "R19") (pin "2") (pinfunction "2_2") (pintype "passive"))
    )
    (net (code "29") (name "Net-(D1-AK)") (class "Default")
      (node (ref "D1") (pin "3") (pinfunction "AK_3") (pintype "passive"))
      (node (ref "R22") (pin "2") (pinfunction "2_2") (pintype "passive"))
      (node (ref "U3") (pin "1") (pinfunction "OUT_1") (pintype "output"))
      (node (ref "U3") (pin "2") (pinfunction "IN-_2") (pintype "input"))
    )
    (net (code "30") (name "Net-(D2-AK)") (class "Default")
      (node (ref "D2") (pin "3") (pinfunction "AK_3") (pintype "passive"))
      (node (ref "R23") (pin "1") (pinfunction "1_1") (pintype "passive"))
      (node (ref "U3") (pin "6") (pinfunction "IN-_6") (pintype "input"))
      (node (ref "U3") (pin "7") (pinfunction "OUT_7") (pintype "output"))
    )
    (net (code "31") (name "Net-(H2-Pad8)") (class "Default")
      (node (ref "H2") (pin "8") (pinfunction "8_8") (pintype "passive"))
      (node (ref "JP2") (pin "2") (pinfunction "2_2") (pintype "passive"))
    )
    (net (code "32") (name "Net-(H3-Pad1)") (class "Default")
      (node (ref "H3") (pin "1") (pinfunction "1_1") (pintype "passive"))
      (node (ref "JP3") (pin "2") (pinfunction "2_2") (pintype "passive"))
    )
    (net (code "33") (name "Net-(MIDI1-Pad4)") (class "Default")
      (node (ref "MIDI1") (pin "4") (pinfunction "4_4") (pintype "passive"))
      (node (ref "R30") (pin "2") (pinfunction "2_2") (pintype "passive"))
    )
    (net (code "34") (name "Net-(MIDI1-Pad5)") (class "Default")
      (node (ref "MIDI1") (pin "5") (pinfunction "5_5") (pintype "passive"))
      (node (ref "R31") (pin "2") (pinfunction "2_2") (pintype "passive"))
    )
    (net (code "35") (name "Net-(R10-Pad1)") (class "Default")
      (node (ref "R10") (pin "1") (pinfunction "1_1") (pintype "passive"))
      (node (ref "R16") (pin "2") (pinfunction "2_2") (pintype "passive"))
      (node (ref "U$1") (pin "4") (pinfunction "4_4") (pintype "bidirectional"))
    )
    (net (code "36") (name "Net-(R11-Pad1)") (class "Default")
      (node (ref "R11") (pin "1") (pinfunction "1_1") (pintype "passive"))
      (node (ref "R17") (pin "2") (pinfunction "2_2") (pintype "passive"))
      (node (ref "U$1") (pin "5") (pinfunction "5_5") (pintype "bidirectional"))
    )
    (net (code "37") (name "Net-(R12-Pad1)") (class "Default")
      (node (ref "R12") (pin "1") (pinfunction "1_1") (pintype "passive"))
      (node (ref "R18") (pin "2") (pinfunction "2_2") (pintype "passive"))
      (node (ref "U$1") (pin "6") (pinfunction "6_6") (pintype "bidirectional"))
    )
    (net (code "38") (name "Net-(R13-Pad2)") (class "Default")
      (node (ref "R13") (pin "2") (pinfunction "2_2") (pintype "passive"))
      (node (ref "R7") (pin "1") (pinfunction "1_1") (pintype "passive"))
      (node (ref "U$1") (pin "1") (pinfunction "1_1") (pintype "bidirectional"))
    )
    (net (code "39") (name "Net-(R14-Pad2)") (class "Default")
      (node (ref "R14") (pin "2") (pinfunction "2_2") (pintype "passive"))
      (node (ref "R8") (pin "1") (pinfunction "1_1") (pintype "passive"))
      (node (ref "U$1") (pin "2") (pinfunction "2_2") (pintype "bidirectional"))
    )
    (net (code "40") (name "Net-(R15-Pad2)") (class "Default")
      (node (ref "R15") (pin "2") (pinfunction "2_2") (pintype "passive"))
      (node (ref "R9") (pin "1") (pinfunction "1_1") (pintype "passive"))
      (node (ref "U$1") (pin "3") (pinfunction "3_3") (pintype "bidirectional"))
    )
    (net (code "41") (name "Net-(R22-Pad1)") (class "Default")
      (node (ref "R22") (pin "1") (pinfunction "1_1") (pintype "passive"))
      (node (ref "U$1") (pin "7") (pinfunction "7_7") (pintype "bidirectional"))
    )
    (net (code "42") (name "Net-(R23-Pad2)") (class "Default")
      (node (ref "R23") (pin "2") (pinfunction "2_2") (pintype "passive"))
      (node (ref "U$1") (pin "8") (pinfunction "8_8") (pintype "bidirectional"))
    )
    (net (code "43") (name "Net-(T1-B)") (class "Default")
      (node (ref "R32") (pin "2") (pinfunction "2_2") (pintype "passive"))
      (node (ref "T1") (pin "1") (pinfunction "B_1") (pintype "passive"))
    )
    (net (code "44") (name "Net-(T1-C)") (class "Default")
      (node (ref "R31") (pin "1") (pinfunction "1_1") (pintype "passive"))
      (node (ref "T1") (pin "3") (pinfunction "C_3") (pintype "passive"))
    )
    (net (code "45") (name "Net-(T2-B)") (class "Default")
      (node (ref "R34") (pin "2") (pinfunction "2_2") (pintype "passive"))
      (node (ref "T2") (pin "1") (pinfunction "B_1") (pintype "passive"))
    )
    (net (code "46") (name "Net-(T2-C)") (class "Default")
      (node (ref "R32") (pin "1") (pinfunction "1_1") (pintype "passive"))
      (node (ref "R33") (pin "1") (pinfunction "1_1") (pintype "passive"))
      (node (ref "T2") (pin "3") (pinfunction "C_3") (pintype "passive"))
    )
    (net (code "47") (name "Net-(U1B-IN+)") (class "Default")
      (node (ref "C4") (pin "1") (pinfunction "1_1") (pintype "passive"))
      (node (ref "H3") (pin "4") (pinfunction "4_4") (pintype "passive"))
      (node (ref "R2") (pin "2") (pinfunction "2_2") (pintype "passive"))
      (node (ref "U1") (pin "5") (pinfunction "IN+_5") (pintype "input"))
    )
    (net (code "48") (name "Net-(U2A-IN+)") (class "Default")
      (node (ref "C5") (pin "1") (pinfunction "1_1") (pintype "passive"))
      (node (ref "H3") (pin "5") (pinfunction "5_5") (pintype "passive"))
      (node (ref "R3") (pin "2") (pinfunction "2_2") (pintype "passive"))
      (node (ref "U2") (pin "3") (pinfunction "IN+_3") (pintype "input"))
    )
    (net (code "49") (name "Net-(U2B-IN+)") (class "Default")
      (node (ref "C6") (pin "1") (pinfunction "1_1") (pintype "passive"))
      (node (ref "H3") (pin "6") (pinfunction "6_6") (pintype "passive"))
      (node (ref "R4") (pin "2") (pinfunction "2_2") (pintype "passive"))
      (node (ref "U2") (pin "5") (pinfunction "IN+_5") (pintype "input"))
    )
    (net (code "50") (name "Net-(U2C-IN+)") (class "Default")
      (node (ref "C7") (pin "1") (pinfunction "1_1") (pintype "passive"))
      (node (ref "H3") (pin "7") (pinfunction "7_7") (pintype "passive"))
      (node (ref "R5") (pin "2") (pinfunction "2_2") (pintype "passive"))
      (node (ref "U2") (pin "10") (pinfunction "IN+_10") (pintype "input"))
    )
    (net (code "51") (name "Net-(U2D-IN+)") (class "Default")
      (node (ref "C8") (pin "1") (pinfunction "1_1") (pintype "passive"))
      (node (ref "H3") (pin "8") (pinfunction "8_8") (pintype "passive"))
      (node (ref "R6") (pin "2") (pinfunction "2_2") (pintype "passive"))
      (node (ref "U2") (pin "12") (pinfunction "IN+_12") (pintype "input"))
    )
    (net (code "52") (name "Net-(U3A-IN+)") (class "Default")
      (node (ref "C13") (pin "1") (pinfunction "1_1") (pintype "passive"))
      (node (ref "R21") (pin "1") (pinfunction "1_1") (pintype "passive"))
      (node (ref "TP3") (pin "TP") (pinfunction "TP_TP") (pintype "input"))
      (node (ref "U3") (pin "3") (pinfunction "IN+_3") (pintype "input"))
    )
    (net (code "53") (name "Net-(U3B-IN+)") (class "Default")
      (node (ref "C14") (pin "1") (pinfunction "1_1") (pintype "passive"))
      (node (ref "R20") (pin "2") (pinfunction "2_2") (pintype "passive"))
      (node (ref "TP2") (pin "TP") (pinfunction "TP_TP") (pintype "input"))
      (node (ref "U3") (pin "5") (pinfunction "IN+_5") (pintype "input"))
    )
    (net (code "54") (name "P1.0") (class "Default")
      (node (ref "C21") (pin "1") (pinfunction "1_1") (pintype "passive"))
      (node (ref "R26") (pin "2") (pinfunction "2_2") (pintype "passive"))
      (node (ref "R29") (pin "1") (pinfunction "1_1") (pintype "passive"))
      (node (ref "U6") (pin "31") (pinfunction "P1.0_31") (pintype "bidirectional"))
    )
    (net (code "55") (name "P1.1") (class "Default")
      (node (ref "H6") (pin "1") (pinfunction "1_1") (pintype "passive"))
      (node (ref "U6") (pin "1") (pinfunction "P1.1_1") (pintype "bidirectional"))
    )
    (net (code "56") (name "P1.2") (class "Default")
      (node (ref "R34") (pin "1") (pinfunction "1_1") (pintype "passive"))
      (node (ref "TP_SER") (pin "TP") (pinfunction "TP_TP") (pintype "input"))
      (node (ref "U6") (pin "2") (pinfunction "P1.2_2") (pintype "bidirectional"))
    )
    (net (code "57") (name "P1.3") (class "Default")
      (node (ref "C26") (pin "1") (pinfunction "1_1") (pintype "passive"))
      (node (ref "R37") (pin "1") (pinfunction "1_1") (pintype "passive"))
      (node (ref "R40") (pin "1") (pinfunction "1_1") (pintype "passive"))
      (node (ref "U6") (pin "3") (pinfunction "P1.3_3") (pintype "bidirectional"))
    )
    (net (code "58") (name "P1.4") (class "Default")
      (node (ref "C25") (pin "1") (pinfunction "1_1") (pintype "passive"))
      (node (ref "R36") (pin "1") (pinfunction "1_1") (pintype "passive"))
      (node (ref "R39") (pin "1") (pinfunction "1_1") (pintype "passive"))
      (node (ref "U6") (pin "4") (pinfunction "P1.4_4") (pintype "bidirectional"))
    )
    (net (code "59") (name "P1.5") (class "Default")
      (node (ref "C24") (pin "1") (pinfunction "1_1") (pintype "passive"))
      (node (ref "R35") (pin "1") (pinfunction "1_1") (pintype "passive"))
      (node (ref "R38") (pin "1") (pinfunction "1_1") (pintype "passive"))
      (node (ref "U6") (pin "5") (pinfunction "P1.5_5") (pintype "bidirectional"))
    )
    (net (code "60") (name "P1.6") (class "Default")
      (node (ref "C19") (pin "1") (pinfunction "1_1") (pintype "passive"))
      (node (ref "R24") (pin "2") (pinfunction "2_2") (pintype "passive"))
      (node (ref "R27") (pin "1") (pinfunction "1_1") (pintype "passive"))
      (node (ref "U6") (pin "21") (pinfunction "P1.6_21") (pintype "bidirectional"))
    )
    (net (code "61") (name "P1.7") (class "Default")
      (node (ref "C20") (pin "1") (pinfunction "1_1") (pintype "passive"))
      (node (ref "R25") (pin "2") (pinfunction "2_2") (pintype "passive"))
      (node (ref "R28") (pin "1") (pinfunction "1_1") (pintype "passive"))
      (node (ref "U6") (pin "22") (pinfunction "P1.7_22") (pintype "bidirectional"))
    )
    (net (code "62") (name "P2.3") (class "Default")
      (node (ref "H7") (pin "1") (pinfunction "1_1") (pintype "passive"))
      (node (ref "U6") (pin "15") (pinfunction "P2.3_15") (pintype "bidirectional"))
    )
    (net (code "63") (name "P2.4") (class "Default")
      (node (ref "H7") (pin "2") (pinfunction "2_2") (pintype "passive"))
      (node (ref "U6") (pin "16") (pinfunction "P2.4_16") (pintype "bidirectional"))
    )
    (net (code "64") (name "P2.5") (class "Default")
      (node (ref "H7") (pin "3") (pinfunction "3_3") (pintype "passive"))
      (node (ref "U6") (pin "17") (pinfunction "P2.5_17") (pintype "input"))
    )
    (net (code "65") (name "P2.6") (class "Default")
      (node (ref "C37") (pin "2") (pinfunction "2_2") (pintype "passive"))
      (node (ref "U6") (pin "26") (pinfunction "P2.6_26") (pintype "bidirectional"))
      (node (ref "X1") (pin "1") (pinfunction "1_1") (pintype "passive"))
    )
    (net (code "66") (name "P2.7") (class "Default")
      (node (ref "C36") (pin "2") (pinfunction "2_2") (pintype "passive"))
      (node (ref "U6") (pin "25") (pinfunction "P2.7_25") (pintype "bidirectional"))
      (node (ref "X1") (pin "2") (pinfunction "2_2") (pintype "passive"))
    )
    (net (code "67") (name "P3.0") (class "Default")
      (node (ref "H6") (pin "3") (pinfunction "3_3") (pintype "passive"))
      (node (ref "U6") (pin "7") (pinfunction "P3.0_7") (pintype "power_in"))
    )
    (net (code "68") (name "P3.1") (class "Default")
      (node (ref "H6") (pin "2") (pinfunction "2_2") (pintype "passive"))
      (node (ref "U6") (pin "6") (pinfunction "P3.1_6") (pintype "power_in"))
    )
    (net (code "69") (name "P3.2") (class "Default")
      (node (ref "H6") (pin "6") (pinfunction "6_6") (pintype "passive"))
      (node (ref "U6") (pin "12") (pinfunction "P3.2_12") (pintype "power_in"))
    )
    (net (code "70") (name "P3.3") (class "Default")
      (node (ref "H6") (pin "7") (pinfunction "7_7") (pintype "passive"))
      (node (ref "U6") (pin "13") (pinfunction "P3.3_13") (pintype "bidirectional"))
    )
    (net (code "71") (name "P3.4") (class "Default")
      (node (ref "H6") (pin "8") (pinfunction "8_8") (pintype "passive"))
      (node (ref "U6") (pin "14") (pinfunction "P3.4_14") (pintype "bidirectional"))
    )
    (net (code "72") (name "P3.5") (class "Default")
      (node (ref "H7") (pin "4") (pinfunction "4_4") (pintype "passive"))
      (node (ref "U6") (pin "18") (pinfunction "P3.5_18") (pintype "bidirectional"))
    )
    (net (code "73") (name "P3.6") (class "Default")
      (node (ref "H7") (pin "5") (pinfunction "5_5") (pintype "passive"))
      (node (ref "U6") (pin "19") (pinfunction "P3.6_19") (pintype "bidirectional"))
    )
    (net (code "74") (name "P3.7") (class "Default")
      (node (ref "H7") (pin "6") (pinfunction "6_6") (pintype "passive"))
      (node (ref "U6") (pin "20") (pinfunction "P3.7_20") (pintype "bidirectional"))
    )
    (net (code "75") (name "TEST") (class "Default")
      (node (ref "H8") (pin "1") (pinfunction "1_1") (pintype "passive"))
      (node (ref "U6") (pin "24") (pinfunction "TEST_24") (pintype "bidirectional"))
    )
    (net (code "76") (name "VIN") (class "Default")
      (node (ref "C1") (pin "+") (pinfunction "+_+") (pintype "passive"))
      (node (ref "C10") (pin "1") (pinfunction "1_1") (pintype "passive"))
      (node (ref "C11") (pin "1") (pinfunction "1_1") (pintype "passive"))
      (node (ref "C12") (pin "1") (pinfunction "1_1") (pintype "passive"))
      (node (ref "C9") (pin "1") (pinfunction "1_1") (pintype "passive"))
      (node (ref "FB1") (pin "2") (pinfunction "2_2") (pintype "bidirectional"))
      (node (ref "U1") (pin "8") (pinfunction "V+_8") (pintype "power_in"))
      (node (ref "U2") (pin "4") (pinfunction "V+_4") (pintype "power_in"))
    )
    (net (code "77") (name "unconnected-(MIDI1-Pad1)") (class "Default")
      (node (ref "MIDI1") (pin "1") (pinfunction "1_1") (pintype "passive"))
    )
    (net (code "78") (name "unconnected-(MIDI1-Pad3)") (class "Default")
      (node (ref "MIDI1") (pin "3") (pinfunction "3_3") (pintype "passive"))
    )
    (net (code "79") (name "unconnected-(U$1-Pad9)") (class "Default")
      (node (ref "U$1") (pin "9") (pinfunction "9_9") (pintype "bidirectional"))
    )
    (net (code "80") (name "unconnected-(U5-ADJ-Pad4)") (class "Default")
      (node (ref "U5") (pin "4") (pinfunction "ADJ_4") (pintype "passive"))
    )
    (net (code "81") (name "unconnected-(U6-NC_1-Pad8)") (class "Default")
      (node (ref "U6") (pin "8") (pinfunction "NC_1_8") (pintype "bidirectional"))
    )
    (net (code "82") (name "unconnected-(U6-NC_2-Pad32)") (class "Default")
      (node (ref "U6") (pin "32") (pinfunction "NC_2_32") (pintype "power_in"))
    )
    (net (code "83") (name "~{RST}") (class "Default")
      (node (ref "C35") (pin "1") (pinfunction "1_1") (pintype "passive"))
      (node (ref "H8") (pin "2") (pinfunction "2_2") (pintype "passive"))
      (node (ref "R41") (pin "2") (pinfunction "2_2") (pintype "passive"))
      (node (ref "U6") (pin "23") (pinfunction "RST_23") (pintype "bidirectional"))
    )
  )
)
